# Sheet1.net
KiCad netlist of a schematic drawn in Altium Designer
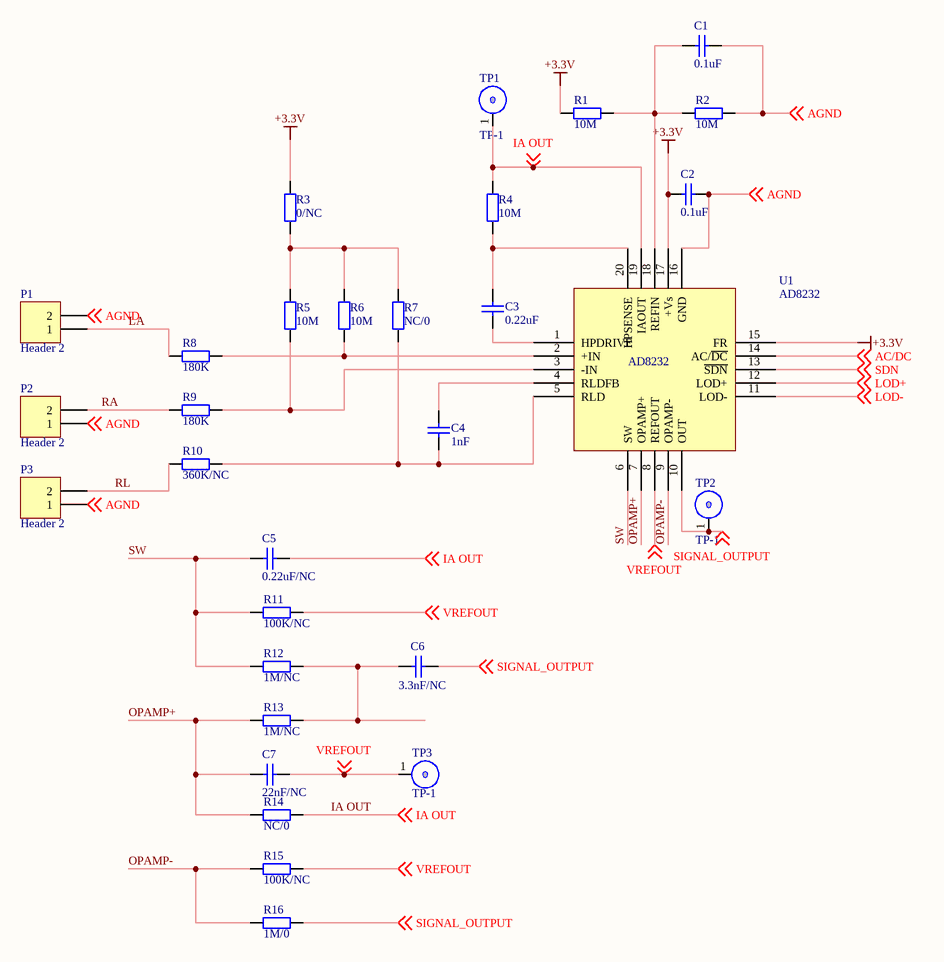
[diagram p0: Sheet1.SchDoc]

(export (version "E")
  (design (tool "Eeschema 10.0.6"))
  (components
    (comp (ref "C1")
      (value "0.1uF")
      (footprint "0603C")
      (description "Capacitor")
      (fields (field (name "PUBLISHER") "Altium Limited"))
      (libsource (lib "ECG.SCHLIB") (part "Cap"))
    )
    (comp (ref "C2")
      (value "0.1uF")
      (footprint "0603C")
      (description "Capacitor")
      (fields (field (name "PUBLISHER") "Altium Limited"))
      (libsource (lib "ECG.SCHLIB") (part "Cap"))
    )
    (comp (ref "C3")
      (value "0.22uF")
      (footprint "0603C")
      (description "Capacitor")
      (fields (field (name "PUBLISHER") "Altium Limited"))
      (libsource (lib "ECG.SCHLIB") (part "Cap"))
    )
    (comp (ref "C4")
      (value "1nF")
      (footprint "0603C")
      (description "Capacitor")
      (fields (field (name "PUBLISHER") "Altium Limited"))
      (libsource (lib "ECG.SCHLIB") (part "Cap"))
    )
    (comp (ref "C5")
      (value "0.22uF/NC")
      (footprint "0603C")
      (description "Capacitor")
      (fields (field (name "PUBLISHER") "Altium Limited"))
      (libsource (lib "ECG.SCHLIB") (part "Cap"))
    )
    (comp (ref "C6")
      (value "3.3nF/NC")
      (footprint "0603C")
      (description "Capacitor")
      (fields (field (name "PUBLISHER") "Altium Limited"))
      (libsource (lib "ECG.SCHLIB") (part "Cap"))
    )
    (comp (ref "C7")
      (value "22nF/NC")
      (footprint "0603C")
      (description "Capacitor")
      (fields (field (name "PUBLISHER") "Altium Limited"))
      (libsource (lib "ECG.SCHLIB") (part "Cap"))
    )
    (comp (ref "P1")
      (value "Header 2")
      (footprint "SIP2")
      (description "Header, 2-Pin")
      (fields (field (name "PUBLISHER") "Altium Limited"))
      (libsource (lib "ECG.SCHLIB") (part "Header 2"))
    )
    (comp (ref "P2")
      (value "Header 2")
      (footprint "SIP2")
      (description "Header, 2-Pin")
      (fields (field (name "PUBLISHER") "Altium Limited"))
      (libsource (lib "ECG.SCHLIB") (part "Header 2"))
    )
    (comp (ref "P3")
      (value "Header 2")
      (footprint "SIP2")
      (description "Header, 2-Pin")
      (fields (field (name "PUBLISHER") "Altium Limited"))
      (libsource (lib "ECG.SCHLIB") (part "Header 2"))
    )
    (comp (ref "R1")
      (value "10M")
      (footprint "0603R")
      (description "Resistor")
      (fields (field (name "PUBLISHER") "Altium Limited"))
      (libsource (lib "") (part "Res2_1"))
    )
    (comp (ref "R2")
      (value "10M")
      (footprint "0603R")
      (description "Resistor")
      (fields (field (name "PUBLISHER") "Altium Limited"))
      (libsource (lib "") (part "Res2_1"))
    )
    (comp (ref "R3")
      (value "0/NC")
      (footprint "0603R")
      (description "Resistor")
      (fields (field (name "PUBLISHER") "Altium Limited"))
      (libsource (lib "ECG.SCHLIB") (part "Res2"))
    )
    (comp (ref "R4")
      (value "10M")
      (footprint "0603R")
      (description "Resistor")
      (fields (field (name "PUBLISHER") "Altium Limited"))
      (libsource (lib "ECG.SCHLIB") (part "Res2"))
    )
    (comp (ref "R5")
      (value "10M")
      (footprint "0603R")
      (description "Resistor")
      (fields (field (name "PUBLISHER") "Altium Limited"))
      (libsource (lib "ECG.SCHLIB") (part "Res2"))
    )
    (comp (ref "R6")
      (value "10M")
      (footprint "0603R")
      (description "Resistor")
      (fields (field (name "PUBLISHER") "Altium Limited"))
      (libsource (lib "ECG.SCHLIB") (part "Res2"))
    )
    (comp (ref "R7")
      (value "NC/0")
      (footprint "0603R")
      (description "Resistor")
      (fields (field (name "PUBLISHER") "Altium Limited"))
      (libsource (lib "ECG.SCHLIB") (part "Res2"))
    )
    (comp (ref "R8")
      (value "180K")
      (footprint "0603R")
      (description "Resistor")
      (fields (field (name "PUBLISHER") "Altium Limited"))
      (libsource (lib "") (part "Res2_2"))
    )
    (comp (ref "R9")
      (value "180K")
      (footprint "0603R")
      (description "Resistor")
      (fields (field (name "PUBLISHER") "Altium Limited"))
      (libsource (lib "") (part "Res2_2"))
    )
    (comp (ref "R10")
      (value "360K/NC")
      (footprint "0603R")
      (description "Resistor")
      (fields (field (name "PUBLISHER") "Altium Limited"))
      (libsource (lib "") (part "Res2_2"))
    )
    (comp (ref "R11")
      (value "100K/NC")
      (footprint "0603R")
      (description "Resistor")
      (fields (field (name "PUBLISHER") "Altium Limited"))
      (libsource (lib "") (part "Res2_2"))
    )
    (comp (ref "R12")
      (value "1M/NC")
      (footprint "0603R")
      (description "Resistor")
      (fields (field (name "PUBLISHER") "Altium Limited"))
      (libsource (lib "") (part "Res2_2"))
    )
    (comp (ref "R13")
      (value "1M/NC")
      (footprint "0603R")
      (description "Resistor")
      (fields (field (name "PUBLISHER") "Altium Limited"))
      (libsource (lib "") (part "Res2_2"))
    )
    (comp (ref "R14")
      (value "NC/0")
      (footprint "0603R")
      (description "Resistor")
      (fields (field (name "PUBLISHER") "Altium Limited"))
      (libsource (lib "") (part "Res2_2"))
    )
    (comp (ref "R15")
      (value "100K/NC")
      (footprint "0603R")
      (description "Resistor")
      (fields (field (name "PUBLISHER") "Altium Limited"))
      (libsource (lib "") (part "Res2_2"))
    )
    (comp (ref "R16")
      (value "1M/0")
      (footprint "0603R")
      (description "Resistor")
      (fields (field (name "PUBLISHER") "Altium Limited"))
      (libsource (lib "") (part "Res2_2"))
    )
    (comp (ref "TP1") (value "TP-1") (footprint "tp-1-1") (libsource (lib "ECG2.0") (part "TP-1")))
    (comp (ref "TP2") (value "TP-1") (footprint "tp-1-1") (libsource (lib "ECG2.0") (part "TP-1")))
    (comp (ref "TP3") (value "TP-1") (footprint "tp-1-1") (libsource (lib "ECG2.0") (part "TP-1")))
    (comp (ref "U1") (value "AD8232") (footprint "QFN-20") (libsource (lib "ECG2.0") (part "AD8232")))
  )
  (nets
    (net (code "1") (name "+3.3V") (class "Default")
      (node (ref "C2") (pin "2") (pinfunction "2_2") (pintype "passive"))
      (node (ref "R1") (pin "2") (pinfunction "2_2") (pintype "passive"))
      (node (ref "R3") (pin "2") (pinfunction "2_2") (pintype "passive"))
      (node (ref "U1") (pin "15") (pinfunction "FR_15") (pintype "passive"))
      (node (ref "U1") (pin "17") (pinfunction "+Vs_17") (pintype "passive"))
    )
    (net (code "3") (name "/LA") (class "Default")
      (node (ref "P1") (pin "1") (pinfunction "1_1") (pintype "passive"))
      (node (ref "R8") (pin "1") (pinfunction "1_1") (pintype "passive"))
    )
    (net (code "4") (name "/OPAMP+") (class "Default")
      (node (ref "C7") (pin "1") (pinfunction "1_1") (pintype "passive"))
      (node (ref "R13") (pin "1") (pinfunction "1_1") (pintype "passive"))
      (node (ref "R14") (pin "1") (pinfunction "1_1") (pintype "passive"))
      (node (ref "U1") (pin "7") (pinfunction "OPAMP+_7") (pintype "passive"))
    )
    (net (code "5") (name "/OPAMP-") (class "Default")
      (node (ref "R15") (pin "1") (pinfunction "1_1") (pintype "passive"))
      (node (ref "R16") (pin "1") (pinfunction "1_1") (pintype "passive"))
      (node (ref "U1") (pin "9") (pinfunction "OPAMP-_9") (pintype "passive"))
    )
    (net (code "6") (name "/RA") (class "Default")
      (node (ref "P2") (pin "2") (pinfunction "2_2") (pintype "passive"))
      (node (ref "R9") (pin "1") (pinfunction "1_1") (pintype "passive"))
    )
    (net (code "7") (name "/RL") (class "Default")
      (node (ref "P3") (pin "2") (pinfunction "2_2") (pintype "passive"))
      (node (ref "R10") (pin "1") (pinfunction "1_1") (pintype "passive"))
    )
    (net (code "8") (name "/SW") (class "Default")
      (node (ref "C5") (pin "1") (pinfunction "1_1") (pintype "passive"))
      (node (ref "R11") (pin "1") (pinfunction "1_1") (pintype "passive"))
      (node (ref "R12") (pin "1") (pinfunction "1_1") (pintype "passive"))
      (node (ref "U1") (pin "6") (pinfunction "SW_6") (pintype "passive"))
    )
    (net (code "9") (name "AC{slash}DC") (class "Default")
      (node (ref "U1") (pin "14") (pinfunction "AC/~{DC}_14") (pintype "passive"))
    )
    (net (code "10") (name "AGND") (class "Default")
      (node (ref "C1") (pin "1") (pinfunction "1_1") (pintype "passive"))
      (node (ref "C2") (pin "1") (pinfunction "1_1") (pintype "passive"))
      (node (ref "P1") (pin "2") (pinfunction "2_2") (pintype "passive"))
      (node (ref "P2") (pin "1") (pinfunction "1_1") (pintype "passive"))
      (node (ref "P3") (pin "1") (pinfunction "1_1") (pintype "passive"))
      (node (ref "R2") (pin "1") (pinfunction "1_1") (pintype "passive"))
      (node (ref "U1") (pin "16") (pinfunction "GND_16") (pintype "passive"))
    )
    (net (code "11") (name "IA OUT") (class "Default")
      (node (ref "C5") (pin "2") (pinfunction "2_2") (pintype "passive"))
      (node (ref "R14") (pin "2") (pinfunction "2_2") (pintype "passive"))
      (node (ref "R4") (pin "2") (pinfunction "2_2") (pintype "passive"))
      (node (ref "TP1") (pin "1") (pintype "passive"))
      (node (ref "U1") (pin "19") (pinfunction "IAOUT_19") (pintype "passive"))
    )
    (net (code "12") (name "LOD+") (class "Default")
      (node (ref "U1") (pin "12") (pinfunction "LOD+_12") (pintype "passive"))
    )
    (net (code "13") (name "LOD-") (class "Default")
      (node (ref "U1") (pin "11") (pinfunction "LOD-_11") (pintype "passive"))
    )
    (net (code "14") (name "Net-(C6-Pad1)") (class "Default")
      (node (ref "C6") (pin "1") (pinfunction "1_1") (pintype "passive"))
      (node (ref "R12") (pin "2") (pinfunction "2_2") (pintype "passive"))
      (node (ref "R13") (pin "2") (pinfunction "2_2") (pintype "passive"))
    )
    (net (code "15") (name "Net-(R3-Pad1)") (class "Default")
      (node (ref "R3") (pin "1") (pinfunction "1_1") (pintype "passive"))
      (node (ref "R5") (pin "2") (pinfunction "2_2") (pintype "passive"))
      (node (ref "R6") (pin "2") (pinfunction "2_2") (pintype "passive"))
      (node (ref "R7") (pin "2") (pinfunction "2_2") (pintype "passive"))
    )
    (net (code "16") (name "Net-(U1-+IN)") (class "Default")
      (node (ref "R6") (pin "1") (pinfunction "1_1") (pintype "passive"))
      (node (ref "R8") (pin "2") (pinfunction "2_2") (pintype "passive"))
      (node (ref "U1") (pin "2") (pinfunction "+IN_2") (pintype "passive"))
    )
    (net (code "17") (name "Net-(U1--IN)") (class "Default")
      (node (ref "R5") (pin "1") (pinfunction "1_1") (pintype "passive"))
      (node (ref "R9") (pin "2") (pinfunction "2_2") (pintype "passive"))
      (node (ref "U1") (pin "3") (pinfunction "-IN_3") (pintype "passive"))
    )
    (net (code "18") (name "Net-(U1-HPDRIVE)") (class "Default")
      (node (ref "C3") (pin "1") (pinfunction "1_1") (pintype "passive"))
      (node (ref "U1") (pin "1") (pinfunction "HPDRIVE_1") (pintype "passive"))
    )
    (net (code "19") (name "Net-(U1-HPSENSE)") (class "Default")
      (node (ref "C3") (pin "2") (pinfunction "2_2") (pintype "passive"))
      (node (ref "R4") (pin "1") (pinfunction "1_1") (pintype "passive"))
      (node (ref "U1") (pin "20") (pinfunction "HPSENSE_20") (pintype "passive"))
    )
    (net (code "20") (name "Net-(U1-REFIN)") (class "Default")
      (node (ref "C1") (pin "2") (pinfunction "2_2") (pintype "passive"))
      (node (ref "R1") (pin "1") (pinfunction "1_1") (pintype "passive"))
      (node (ref "R2") (pin "2") (pinfunction "2_2") (pintype "passive"))
      (node (ref "U1") (pin "18") (pinfunction "REFIN_18") (pintype "passive"))
    )
    (net (code "21") (name "Net-(U1-RLD)") (class "Default")
      (node (ref "C4") (pin "1") (pinfunction "1_1") (pintype "passive"))
      (node (ref "R10") (pin "2") (pinfunction "2_2") (pintype "passive"))
      (node (ref "R7") (pin "1") (pinfunction "1_1") (pintype "passive"))
      (node (ref "U1") (pin "5") (pinfunction "RLD_5") (pintype "passive"))
    )
    (net (code "22") (name "Net-(U1-RLDFB)") (class "Default")
      (node (ref "C4") (pin "2") (pinfunction "2_2") (pintype "passive"))
      (node (ref "U1") (pin "4") (pinfunction "RLDFB_4") (pintype "passive"))
    )
    (net (code "23") (name "SDN") (class "Default")
      (node (ref "U1") (pin "13") (pinfunction "~{SDN}_13") (pintype "passive"))
    )
    (net (code "24") (name "SIGNAL_OUTPUT") (class "Default")
      (node (ref "C6") (pin "2") (pinfunction "2_2") (pintype "passive"))
      (node (ref "R16") (pin "2") (pinfunction "2_2") (pintype "passive"))
      (node (ref "TP2") (pin "1") (pintype "passive"))
      (node (ref "U1") (pin "10") (pinfunction "OUT_10") (pintype "passive"))
    )
    (net (code "25") (name "VREFOUT") (class "Default")
      (node (ref "C7") (pin "2") (pinfunction "2_2") (pintype "passive"))
      (node (ref "R11") (pin "2") (pinfunction "2_2") (pintype "passive"))
      (node (ref "R15") (pin "2") (pinfunction "2_2") (pintype "passive"))
      (node (ref "TP3") (pin "1") (pintype "passive"))
      (node (ref "U1") (pin "8") (pinfunction "REFOUT_8") (pintype "passive"))
    )
  )
)
